# Sheet2.net
KiCad netlist of a schematic drawn in Altium Designer
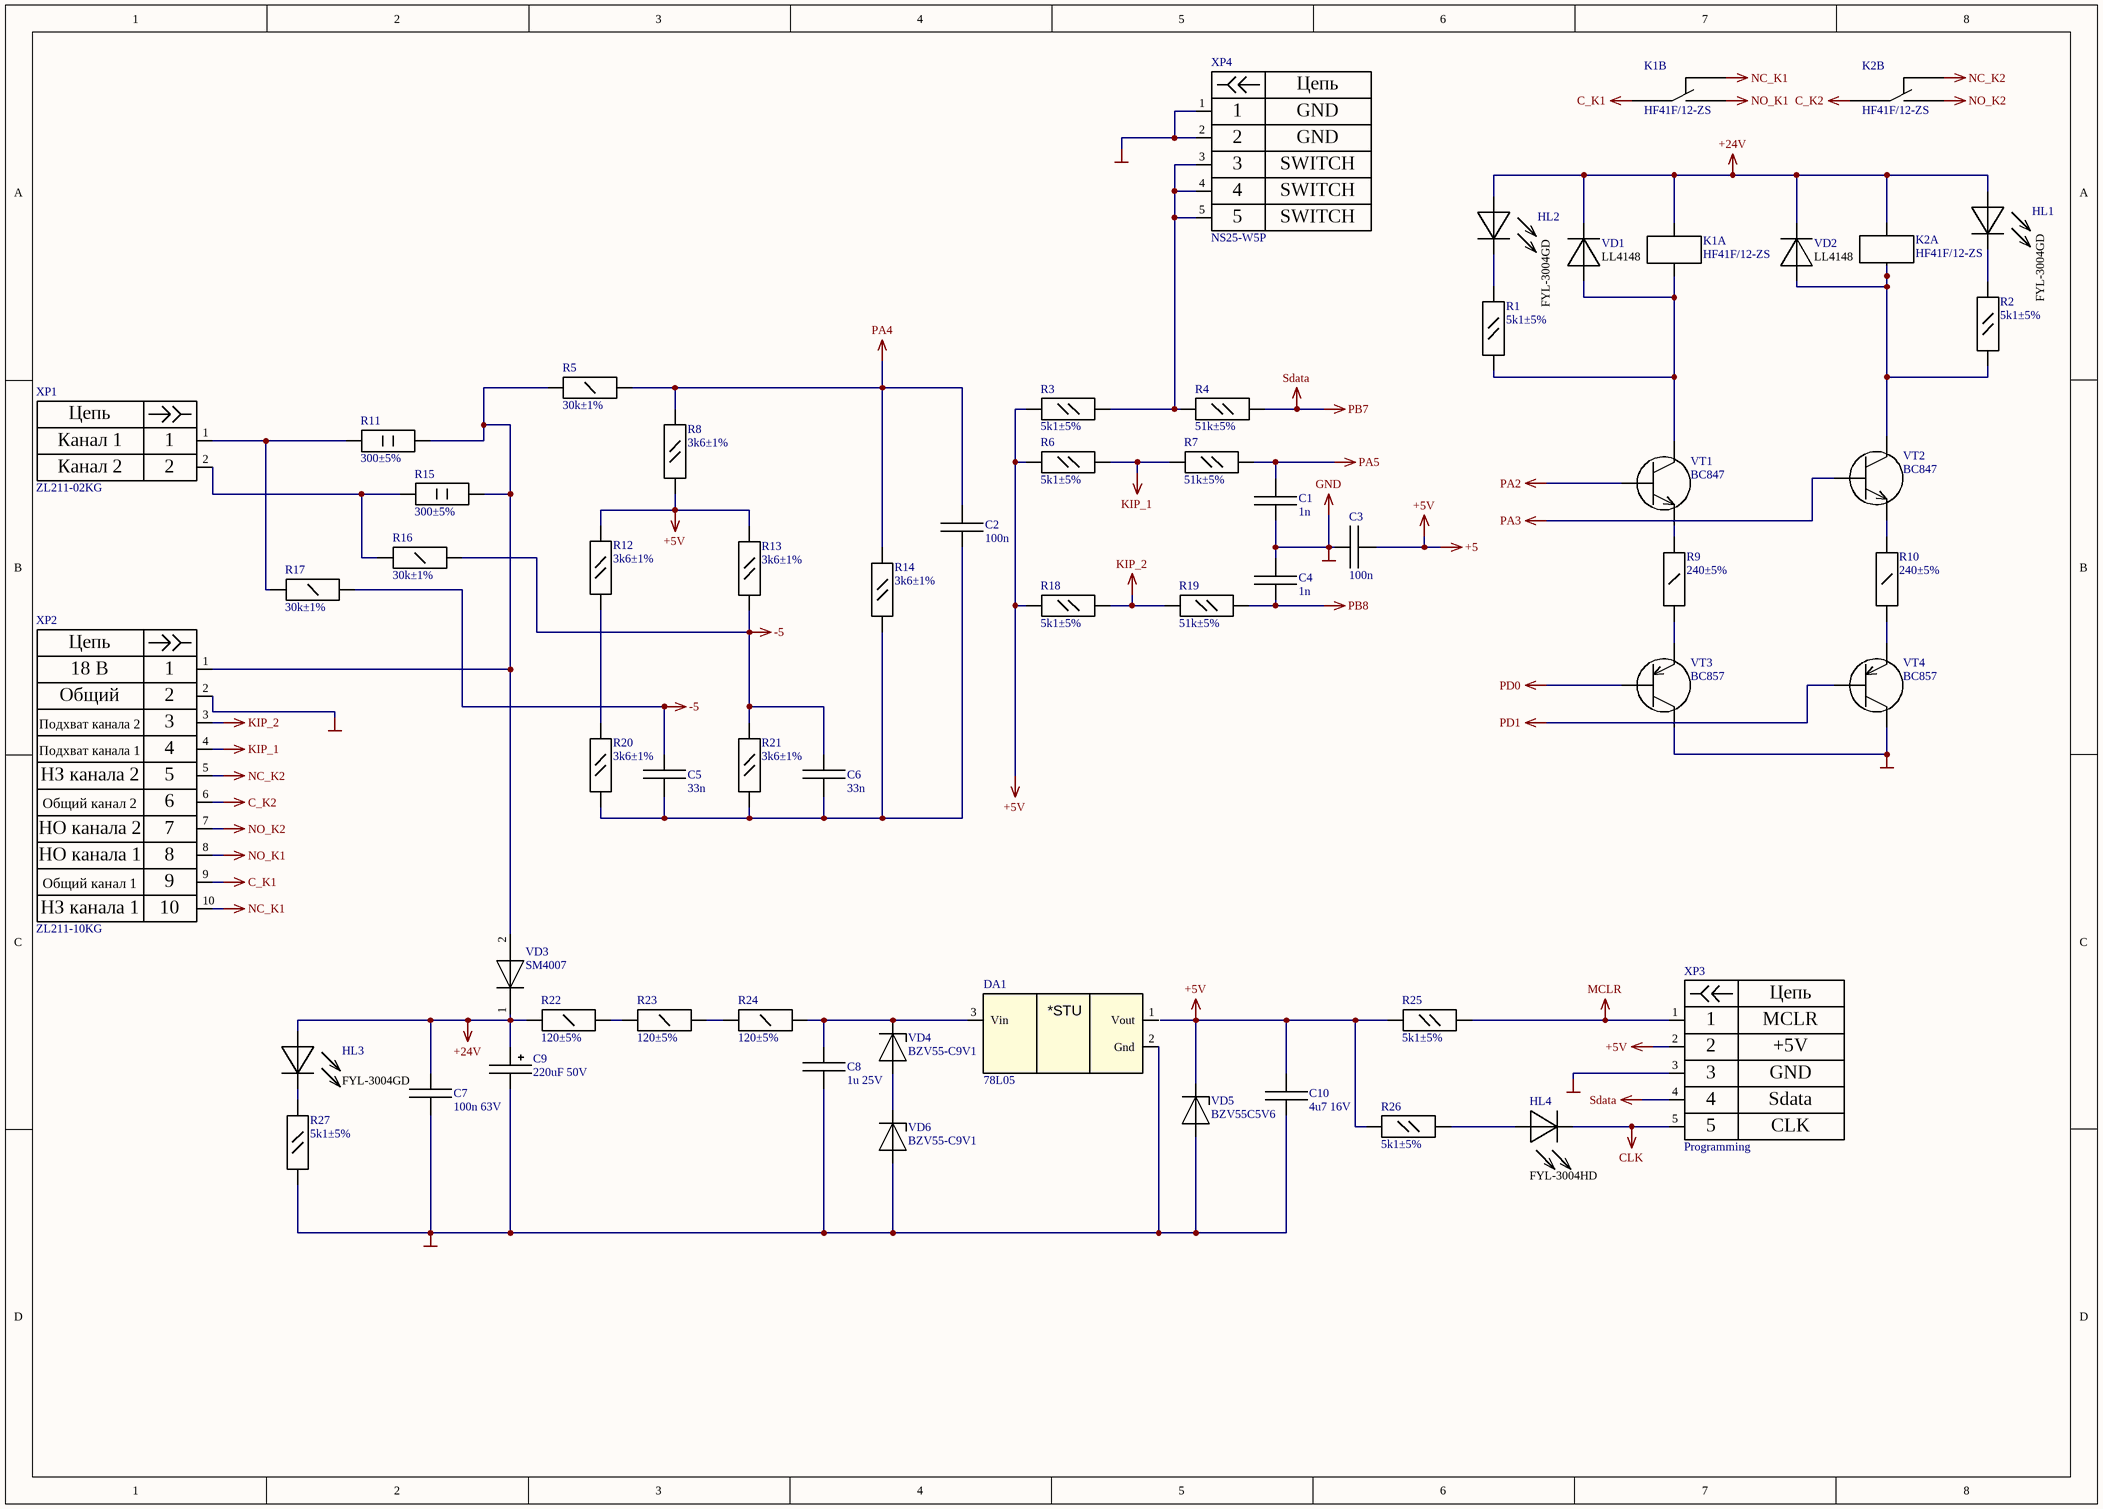
[diagram p0: Sheet2.SchDoc]

(export (version "E")
  (design (tool "Eeschema 10.0.6"))
  (components
    (comp (ref "C1") (value "1n") (footprint "Cap Ceramic 0805") (libsource (lib "Россыпь") (part "CerCap")))
    (comp (ref "C2")
      (value "100n")
      (footprint "Cap Ceramic 0805")
      (libsource (lib "Россыпь") (part "CerCap"))
    )
    (comp (ref "C3")
      (value "100n")
      (footprint "Cap Ceramic 0805")
      (libsource (lib "Россыпь") (part "CerCap"))
    )
    (comp (ref "C4") (value "1n") (footprint "Cap Ceramic 0805") (libsource (lib "Россыпь") (part "CerCap")))
    (comp (ref "C5") (value "33n") (footprint "Cap Ceramic 0805") (libsource (lib "Россыпь") (part "CerCap")))
    (comp (ref "C6") (value "33n") (footprint "Cap Ceramic 0805") (libsource (lib "Россыпь") (part "CerCap")))
    (comp (ref "C7")
      (value "100n 63V")
      (footprint "Cap Ceramic 0805")
      (libsource (lib "Россыпь") (part "CerCap"))
    )
    (comp (ref "C8")
      (value "1u 25V")
      (footprint "Cap Ceramic 0805")
      (libsource (lib "Россыпь") (part "CerCap"))
    )
    (comp (ref "C9")
      (value "220uF 50V")
      (footprint "Cap electro d5x2.05mm")
      (libsource (lib "Россыпь") (part "ECap"))
    )
    (comp (ref "C10")
      (value "4u7 16V")
      (footprint "Cap Ceramic 0805")
      (libsource (lib "Россыпь") (part "CerCap"))
    )
    (comp (ref "DA1") (value "78L05") (footprint "SOT-89") (libsource (lib "Россыпь") (part "78L05")))
    (comp (ref "HL1") (value "FYL-3004GD") (footprint "LED 0805") (libsource (lib "Россыпь") (part "LED")))
    (comp (ref "HL2") (value "FYL-3004GD") (footprint "LED 0805") (libsource (lib "Россыпь") (part "LED")))
    (comp (ref "HL3") (value "FYL-3004GD") (footprint "LED 0805") (libsource (lib "Россыпь") (part "LED")))
    (comp (ref "HL4") (value "FYL-3004HD") (footprint "LED 0805") (libsource (lib "Россыпь") (part "LED")))
    (comp (ref "K1")
      (value "HF41F/12-ZS")
      (footprint "HF41F_12-ZS")
      (libsource (lib "Schlib1") (part "HF41F_12-ZS"))
    )
    (comp (ref "K2")
      (value "HF41F/12-ZS")
      (footprint "HF41F_12-ZS")
      (libsource (lib "Schlib1") (part "HF41F_12-ZS"))
    )
    (comp (ref "R1")
      (value "5k1±5%")
      (footprint "Resistor 0805")
      (libsource (lib "Россыпь") (part "Resistor 0,125W"))
    )
    (comp (ref "R2")
      (value "5k1±5%")
      (footprint "Resistor 0805")
      (libsource (lib "Россыпь") (part "Resistor 0,125W"))
    )
    (comp (ref "R3")
      (value "5k1±5%")
      (footprint "Resistor 0805")
      (libsource (lib "Россыпь") (part "Resistor 0,125W"))
    )
    (comp (ref "R4")
      (value "51k±5%")
      (footprint "Resistor 0805")
      (libsource (lib "Россыпь") (part "Resistor 0,125W"))
    )
    (comp (ref "R5")
      (value "30k±1%")
      (footprint "Resistor 1206")
      (libsource (lib "Schlib1") (part "Resistor 0.5W"))
    )
    (comp (ref "R6")
      (value "5k1±5%")
      (footprint "Resistor 0805")
      (libsource (lib "Россыпь") (part "Resistor 0,125W"))
    )
    (comp (ref "R7")
      (value "51k±5%")
      (footprint "Resistor 0805")
      (libsource (lib "Россыпь") (part "Resistor 0,125W"))
    )
    (comp (ref "R8")
      (value "3k6±1%")
      (footprint "Resistor 0805")
      (libsource (lib "Россыпь") (part "Resistor 0,125W"))
    )
    (comp (ref "R9")
      (value "240±5%")
      (footprint "Resistor 1206")
      (libsource (lib "Schlib1") (part "Resistor 0,25W"))
    )
    (comp (ref "R10")
      (value "240±5%")
      (footprint "Resistor 1206")
      (libsource (lib "Schlib1") (part "Resistor 0,25W"))
    )
    (comp (ref "R11")
      (value "300±5%")
      (footprint "Resistor 2W d5.08x20.32 axial")
      (libsource (lib "Россыпь") (part "Resistor 2W"))
    )
    (comp (ref "R12")
      (value "3k6±1%")
      (footprint "Resistor 0805")
      (libsource (lib "Россыпь") (part "Resistor 0,125W"))
    )
    (comp (ref "R13")
      (value "3k6±1%")
      (footprint "Resistor 0805")
      (libsource (lib "Россыпь") (part "Resistor 0,125W"))
    )
    (comp (ref "R14")
      (value "3k6±1%")
      (footprint "Resistor 0805")
      (libsource (lib "Россыпь") (part "Resistor 0,125W"))
    )
    (comp (ref "R15")
      (value "300±5%")
      (footprint "Resistor 2W d5.08x20.32 axial")
      (libsource (lib "Россыпь") (part "Resistor 2W"))
    )
    (comp (ref "R16")
      (value "30k±1%")
      (footprint "Resistor 1206")
      (libsource (lib "Schlib1") (part "Resistor 0.5W"))
    )
    (comp (ref "R17")
      (value "30k±1%")
      (footprint "Resistor 1206")
      (libsource (lib "Schlib1") (part "Resistor 0.5W"))
    )
    (comp (ref "R18")
      (value "5k1±5%")
      (footprint "Resistor 0805")
      (libsource (lib "Россыпь") (part "Resistor 0,125W"))
    )
    (comp (ref "R19")
      (value "51k±5%")
      (footprint "Resistor 0805")
      (libsource (lib "Россыпь") (part "Resistor 0,125W"))
    )
    (comp (ref "R20")
      (value "3k6±1%")
      (footprint "Resistor 0805")
      (libsource (lib "Россыпь") (part "Resistor 0,125W"))
    )
    (comp (ref "R21")
      (value "3k6±1%")
      (footprint "Resistor 0805")
      (libsource (lib "Россыпь") (part "Resistor 0,125W"))
    )
    (comp (ref "R22")
      (value "120±5%")
      (footprint "Resistor 1206")
      (libsource (lib "Россыпь") (part "Resistor 0,25W"))
    )
    (comp (ref "R23")
      (value "120±5%")
      (footprint "Resistor 1206")
      (libsource (lib "Россыпь") (part "Resistor 0,25W"))
    )
    (comp (ref "R24")
      (value "120±5%")
      (footprint "Resistor 1206")
      (libsource (lib "Россыпь") (part "Resistor 0,25W"))
    )
    (comp (ref "R25")
      (value "5k1±5%")
      (footprint "Resistor 0805")
      (libsource (lib "Schlib1") (part "Resistor 0,125W"))
    )
    (comp (ref "R26")
      (value "5k1±5%")
      (footprint "Resistor 0805")
      (libsource (lib "Schlib1") (part "Resistor 0,125W"))
    )
    (comp (ref "R27")
      (value "5k1±5%")
      (footprint "Resistor 0805")
      (libsource (lib "Schlib1") (part "Resistor 0,125W"))
    )
    (comp (ref "VD1") (value "LL4148") (footprint "SOD80C") (libsource (lib "Россыпь") (part "LL4148")))
    (comp (ref "VD2") (value "LL4148") (footprint "SOD80C") (libsource (lib "Россыпь") (part "LL4148")))
    (comp (ref "VD3") (value "SM4007") (footprint "SM4007") (libsource (lib "Schlib1") (part "SM4007")))
    (comp (ref "VD4")
      (value "BZV55-C9V1")
      (footprint "BZV55C9V1")
      (libsource (lib "Schlib1") (part "BZV55C9V1"))
    )
    (comp (ref "VD5")
      (value "BZV55C5V6")
      (footprint "BZV55C5V6")
      (libsource (lib "Schlib1") (part "BZV55C5V6"))
    )
    (comp (ref "VD6")
      (value "BZV55-C9V1")
      (footprint "BZV55C9V1")
      (libsource (lib "Schlib1") (part "BZV55C9V1"))
    )
    (comp (ref "VT1") (value "BC847") (footprint "SOT-23-3") (libsource (lib "Россыпь") (part "BC847")))
    (comp (ref "VT2") (value "BC847") (footprint "SOT-23-3") (libsource (lib "Россыпь") (part "BC847")))
    (comp (ref "VT3") (value "BC857") (footprint "SOT-23-3") (libsource (lib "Россыпь") (part "BC857")))
    (comp (ref "VT4") (value "BC857") (footprint "SOT-23-3") (libsource (lib "Россыпь") (part "BC857")))
    (comp (ref "XP1")
      (value "ZL211-02KG")
      (footprint "Pins 1x2")
      (fields (field (name "NAME1") "Канал 1") (field (name "NAME") "Цепь") (field (name "NAME2") "Канал 2"))
      (libsource (lib "Россыпь") (part "Pins 1x2"))
    )
    (comp (ref "XP2")
      (value "ZL211-10KG")
      (footprint "Pins 1x10")
      (fields
        (field (name "NAME1") "18 В")
        (field (name "NAME2") "Общий")
        (field (name "NAME3") "Подхват канала 2")
        (field (name "NAME") "Цепь")
        (field (name "NAME4") "Подхват канала 1")
        (field (name "NAME5") "НЗ канала 2")
        (field (name "NAME6") "Общий канал 2")
        (field (name "NAME7") "НО канала 2")
        (field (name "NAME8") "НО канала 1")
        (field (name "NAME9") "Общий канал 1")
        (field (name "NAME10") "НЗ канала 1")
      )
      (libsource (lib "Россыпь") (part "Pins 1x10"))
    )
    (comp (ref "XP3")
      (value "Programming")
      (footprint "WF-05")
      (fields
        (field (name "NAME1") "MCLR")
        (field (name "NAME") "Цепь")
        (field (name "NAME2") "+5V")
        (field (name "NAME3") "GND")
        (field (name "NAME4") "Sdata")
        (field (name "NAME5") "CLK")
      )
      (libsource (lib "Россыпь") (part "Pins 1x5"))
    )
    (comp (ref "XP4")
      (value "NS25-W5P")
      (footprint "WF-05")
      (fields
        (field (name "NAME1") "GND")
        (field (name "NAME") "Цепь")
        (field (name "NAME2") "GND")
        (field (name "NAME3") "SWITCH")
        (field (name "NAME4") "SWITCH")
        (field (name "NAME5") "SWITCH")
      )
      (libsource (lib "Россыпь") (part "Pins 1x5"))
    )
  )
  (nets
    (net (code "1") (name "+5") (class "Default")
      (node (ref "C10") (pin "2") (pinfunction "2_2") (pintype "passive"))
      (node (ref "C3") (pin "2") (pinfunction "2_2") (pintype "passive"))
      (node (ref "R12") (pin "2") (pinfunction "2_2") (pintype "passive"))
      (node (ref "R13") (pin "2") (pinfunction "2_2") (pintype "passive"))
      (node (ref "R18") (pin "1") (pinfunction "1_1") (pintype "passive"))
      (node (ref "R25") (pin "1") (pinfunction "1_1") (pintype "passive"))
      (node (ref "R26") (pin "1") (pinfunction "1_1") (pintype "passive"))
      (node (ref "R3") (pin "1") (pinfunction "1_1") (pintype "passive"))
      (node (ref "R6") (pin "1") (pinfunction "1_1") (pintype "passive"))
      (node (ref "R8") (pin "1") (pinfunction "1_1") (pintype "passive"))
      (node (ref "VD5") (pin "9") (pinfunction "9_9") (pintype "passive"))
      (node (ref "XP3") (pin "2") (pinfunction "2_2") (pintype "passive"))
    )
    (net (code "2") (name "+24V") (class "Default")
      (node (ref "C7") (pin "1") (pinfunction "1_1") (pintype "passive"))
      (node (ref "C9") (pin "2") (pinfunction "2_2") (pintype "passive"))
      (node (ref "HL1") (pin "1") (pinfunction "A_1") (pintype "passive"))
      (node (ref "HL2") (pin "1") (pinfunction "A_1") (pintype "passive"))
      (node (ref "HL3") (pin "1") (pinfunction "A_1") (pintype "passive"))
      (node (ref "K1") (pin "10") (pinfunction "10_10") (pintype "passive"))
      (node (ref "K2") (pin "10") (pinfunction "10_10") (pintype "passive"))
      (node (ref "R22") (pin "1") (pinfunction "1_1") (pintype "passive"))
      (node (ref "VD1") (pin "2") (pinfunction "K_2") (pintype "passive"))
      (node (ref "VD2") (pin "2") (pinfunction "K_2") (pintype "passive"))
      (node (ref "VD3") (pin "1") (pinfunction "2_1") (pintype "passive"))
    )
    (net (code "3") (name "-5") (class "Default")
      (node (ref "C1") (pin "1") (pinfunction "1_1") (pintype "passive"))
      (node (ref "C10") (pin "1") (pinfunction "1_1") (pintype "passive"))
      (node (ref "C3") (pin "1") (pinfunction "1_1") (pintype "passive"))
      (node (ref "C4") (pin "2") (pinfunction "2_2") (pintype "passive"))
      (node (ref "C5") (pin "1") (pinfunction "1_1") (pintype "passive"))
      (node (ref "C6") (pin "1") (pinfunction "1_1") (pintype "passive"))
      (node (ref "C7") (pin "2") (pinfunction "2_2") (pintype "passive"))
      (node (ref "C8") (pin "2") (pinfunction "2_2") (pintype "passive"))
      (node (ref "C9") (pin "1") (pinfunction "1_1") (pintype "passive"))
      (node (ref "DA1") (pin "2") (pinfunction "Gnd_2") (pintype "passive"))
      (node (ref "R13") (pin "1") (pinfunction "1_1") (pintype "passive"))
      (node (ref "R16") (pin "2") (pinfunction "2_2") (pintype "passive"))
      (node (ref "R17") (pin "2") (pinfunction "2_2") (pintype "passive"))
      (node (ref "R21") (pin "2") (pinfunction "2_2") (pintype "passive"))
      (node (ref "R27") (pin "1") (pinfunction "1_1") (pintype "passive"))
      (node (ref "VD5") (pin "8") (pinfunction "8_8") (pintype "passive"))
      (node (ref "VD6") (pin "8") (pinfunction "8_8") (pintype "passive"))
      (node (ref "VT3") (pin "3") (pinfunction "K_3") (pintype "passive"))
      (node (ref "VT4") (pin "3") (pinfunction "K_3") (pintype "passive"))
      (node (ref "XP2") (pin "2") (pinfunction "2_2") (pintype "passive"))
      (node (ref "XP3") (pin "3") (pinfunction "3_3") (pintype "passive"))
      (node (ref "XP4") (pin "1") (pinfunction "1_1") (pintype "passive"))
      (node (ref "XP4") (pin "2") (pinfunction "2_2") (pintype "passive"))
    )
    (net (code "4") (name "CLK") (class "Default")
      (node (ref "HL4") (pin "2") (pinfunction "K_2") (pintype "passive"))
      (node (ref "XP3") (pin "5") (pinfunction "5_5") (pintype "passive"))
    )
    (net (code "5") (name "C_K1") (class "Default")
      (node (ref "K1") (pin "14") (pinfunction "14_14") (pintype "passive"))
      (node (ref "XP2") (pin "9") (pinfunction "9_9") (pintype "passive"))
    )
    (net (code "6") (name "C_K2") (class "Default")
      (node (ref "K2") (pin "14") (pinfunction "14_14") (pintype "passive"))
      (node (ref "XP2") (pin "6") (pinfunction "6_6") (pintype "passive"))
    )
    (net (code "7") (name "KIP_1") (class "Default")
      (node (ref "R6") (pin "2") (pinfunction "2_2") (pintype "passive"))
      (node (ref "R7") (pin "1") (pinfunction "1_1") (pintype "passive"))
      (node (ref "XP2") (pin "4") (pinfunction "4_4") (pintype "passive"))
    )
    (net (code "8") (name "KIP_2") (class "Default")
      (node (ref "R18") (pin "2") (pinfunction "2_2") (pintype "passive"))
      (node (ref "R19") (pin "1") (pinfunction "1_1") (pintype "passive"))
      (node (ref "XP2") (pin "3") (pinfunction "3_3") (pintype "passive"))
    )
    (net (code "9") (name "MCLR") (class "Default")
      (node (ref "R25") (pin "2") (pinfunction "2_2") (pintype "passive"))
      (node (ref "XP3") (pin "1") (pinfunction "1_1") (pintype "passive"))
    )
    (net (code "10") (name "NC_K1") (class "Default")
      (node (ref "K1") (pin "12") (pinfunction "12_12") (pintype "passive"))
      (node (ref "XP2") (pin "10") (pinfunction "10_10") (pintype "passive"))
    )
    (net (code "11") (name "NC_K2") (class "Default")
      (node (ref "K2") (pin "12") (pinfunction "12_12") (pintype "passive"))
      (node (ref "XP2") (pin "5") (pinfunction "5_5") (pintype "passive"))
    )
    (net (code "12") (name "NO_K1") (class "Default")
      (node (ref "K1") (pin "13") (pinfunction "13_13") (pintype "passive"))
      (node (ref "XP2") (pin "8") (pinfunction "8_8") (pintype "passive"))
    )
    (net (code "13") (name "NO_K2") (class "Default")
      (node (ref "K2") (pin "13") (pinfunction "13_13") (pintype "passive"))
      (node (ref "XP2") (pin "7") (pinfunction "7_7") (pintype "passive"))
    )
    (net (code "14") (name "Net-(C2-Pad1)") (class "Default")
      (node (ref "C2") (pin "1") (pinfunction "1_1") (pintype "passive"))
      (node (ref "C5") (pin "2") (pinfunction "2_2") (pintype "passive"))
      (node (ref "C6") (pin "2") (pinfunction "2_2") (pintype "passive"))
      (node (ref "R14") (pin "1") (pinfunction "1_1") (pintype "passive"))
      (node (ref "R20") (pin "1") (pinfunction "1_1") (pintype "passive"))
      (node (ref "R21") (pin "1") (pinfunction "1_1") (pintype "passive"))
    )
    (net (code "15") (name "Net-(DA1-Vin)") (class "Default")
      (node (ref "C8") (pin "1") (pinfunction "1_1") (pintype "passive"))
      (node (ref "DA1") (pin "3") (pinfunction "Vin_3") (pintype "passive"))
      (node (ref "R24") (pin "2") (pinfunction "2_2") (pintype "passive"))
      (node (ref "VD4") (pin "9") (pinfunction "9_9") (pintype "passive"))
    )
    (net (code "16") (name "Net-(HL1-K)") (class "Default")
      (node (ref "HL1") (pin "2") (pinfunction "K_2") (pintype "passive"))
      (node (ref "R2") (pin "2") (pinfunction "2_2") (pintype "passive"))
    )
    (net (code "17") (name "Net-(HL2-K)") (class "Default")
      (node (ref "HL2") (pin "2") (pinfunction "K_2") (pintype "passive"))
      (node (ref "R1") (pin "2") (pinfunction "2_2") (pintype "passive"))
    )
    (net (code "18") (name "Net-(HL3-K)") (class "Default")
      (node (ref "HL3") (pin "2") (pinfunction "K_2") (pintype "passive"))
      (node (ref "R27") (pin "2") (pinfunction "2_2") (pintype "passive"))
    )
    (net (code "19") (name "Net-(HL4-A)") (class "Default")
      (node (ref "HL4") (pin "1") (pinfunction "A_1") (pintype "passive"))
      (node (ref "R26") (pin "2") (pinfunction "2_2") (pintype "passive"))
    )
    (net (code "20") (name "Net-(R3-Pad2)") (class "Default")
      (node (ref "R3") (pin "2") (pinfunction "2_2") (pintype "passive"))
      (node (ref "R4") (pin "1") (pinfunction "1_1") (pintype "passive"))
      (node (ref "XP4") (pin "3") (pinfunction "3_3") (pintype "passive"))
      (node (ref "XP4") (pin "4") (pinfunction "4_4") (pintype "passive"))
      (node (ref "XP4") (pin "5") (pinfunction "5_5") (pintype "passive"))
    )
    (net (code "21") (name "Net-(R11-Pad1)") (class "Default")
      (node (ref "R11") (pin "1") (pinfunction "1_1") (pintype "passive"))
      (node (ref "R17") (pin "1") (pinfunction "1_1") (pintype "passive"))
      (node (ref "XP1") (pin "1") (pinfunction "1_1") (pintype "passive"))
    )
    (net (code "22") (name "Net-(R12-Pad1)") (class "Default")
      (node (ref "R12") (pin "1") (pinfunction "1_1") (pintype "passive"))
      (node (ref "R20") (pin "2") (pinfunction "2_2") (pintype "passive"))
    )
    (net (code "23") (name "Net-(R15-Pad1)") (class "Default")
      (node (ref "R15") (pin "1") (pinfunction "1_1") (pintype "passive"))
      (node (ref "R16") (pin "1") (pinfunction "1_1") (pintype "passive"))
      (node (ref "XP1") (pin "2") (pinfunction "2_2") (pintype "passive"))
    )
    (net (code "24") (name "Net-(R22-Pad2)") (class "Default")
      (node (ref "R22") (pin "2") (pinfunction "2_2") (pintype "passive"))
      (node (ref "R23") (pin "1") (pinfunction "1_1") (pintype "passive"))
    )
    (net (code "25") (name "Net-(R23-Pad2)") (class "Default")
      (node (ref "R23") (pin "2") (pinfunction "2_2") (pintype "passive"))
      (node (ref "R24") (pin "1") (pinfunction "1_1") (pintype "passive"))
    )
    (net (code "26") (name "Net-(VD1-A)") (class "Default")
      (node (ref "K1") (pin "11") (pinfunction "11_11") (pintype "passive"))
      (node (ref "R1") (pin "1") (pinfunction "1_1") (pintype "passive"))
      (node (ref "VD1") (pin "1") (pinfunction "A_1") (pintype "passive"))
      (node (ref "VT1") (pin "3") (pinfunction "K_3") (pintype "passive"))
    )
    (net (code "27") (name "Net-(VD2-A)") (class "Default")
      (node (ref "K2") (pin "11") (pinfunction "11_11") (pintype "passive"))
      (node (ref "R2") (pin "1") (pinfunction "1_1") (pintype "passive"))
      (node (ref "VD2") (pin "1") (pinfunction "A_1") (pintype "passive"))
      (node (ref "VT2") (pin "3") (pinfunction "K_3") (pintype "passive"))
    )
    (net (code "28") (name "Net-(VD3-4)") (class "Default")
      (node (ref "R11") (pin "2") (pinfunction "2_2") (pintype "passive"))
      (node (ref "R15") (pin "2") (pinfunction "2_2") (pintype "passive"))
      (node (ref "R5") (pin "1") (pinfunction "1_1") (pintype "passive"))
      (node (ref "VD3") (pin "2") (pinfunction "4_2") (pintype "passive"))
      (node (ref "XP2") (pin "1") (pinfunction "1_1") (pintype "passive"))
    )
    (net (code "29") (name "Net-(VD4-Pad8)") (class "Default")
      (node (ref "VD4") (pin "8") (pinfunction "8_8") (pintype "passive"))
      (node (ref "VD6") (pin "9") (pinfunction "9_9") (pintype "passive"))
    )
    (net (code "30") (name "Net-(VT1-E)") (class "Default")
      (node (ref "R9") (pin "2") (pinfunction "2_2") (pintype "passive"))
      (node (ref "VT1") (pin "2") (pinfunction "E_2") (pintype "passive"))
    )
    (net (code "31") (name "Net-(VT2-E)") (class "Default")
      (node (ref "R10") (pin "2") (pinfunction "2_2") (pintype "passive"))
      (node (ref "VT2") (pin "2") (pinfunction "E_2") (pintype "passive"))
    )
    (net (code "32") (name "Net-(VT3-E)") (class "Default")
      (node (ref "R9") (pin "1") (pinfunction "1_1") (pintype "passive"))
      (node (ref "VT3") (pin "2") (pinfunction "E_2") (pintype "passive"))
    )
    (net (code "33") (name "Net-(VT4-E)") (class "Default")
      (node (ref "R10") (pin "1") (pinfunction "1_1") (pintype "passive"))
      (node (ref "VT4") (pin "2") (pinfunction "E_2") (pintype "passive"))
    )
    (net (code "34") (name "PA2") (class "Default")
      (node (ref "VT1") (pin "1") (pinfunction "B_1") (pintype "passive"))
    )
    (net (code "35") (name "PA3") (class "Default")
      (node (ref "VT2") (pin "1") (pinfunction "B_1") (pintype "passive"))
    )
    (net (code "36") (name "PA4") (class "Default")
      (node (ref "C2") (pin "2") (pinfunction "2_2") (pintype "passive"))
      (node (ref "R14") (pin "2") (pinfunction "2_2") (pintype "passive"))
      (node (ref "R5") (pin "2") (pinfunction "2_2") (pintype "passive"))
      (node (ref "R8") (pin "2") (pinfunction "2_2") (pintype "passive"))
    )
    (net (code "37") (name "PA5") (class "Default")
      (node (ref "C1") (pin "2") (pinfunction "2_2") (pintype "passive"))
      (node (ref "R7") (pin "2") (pinfunction "2_2") (pintype "passive"))
    )
    (net (code "38") (name "PB7") (class "Default")
      (node (ref "R4") (pin "2") (pinfunction "2_2") (pintype "passive"))
      (node (ref "XP3") (pin "4") (pinfunction "4_4") (pintype "passive"))
    )
    (net (code "39") (name "PB8") (class "Default")
      (node (ref "C4") (pin "1") (pinfunction "1_1") (pintype "passive"))
      (node (ref "R19") (pin "2") (pinfunction "2_2") (pintype "passive"))
    )
    (net (code "40") (name "PD0") (class "Default")
      (node (ref "VT3") (pin "1") (pinfunction "B_1") (pintype "passive"))
    )
    (net (code "41") (name "PD1") (class "Default")
      (node (ref "VT4") (pin "1") (pinfunction "B_1") (pintype "passive"))
    )
    (net (code "42") (name "unconnected-(DA1-Vout-Pad1)") (class "Default")
      (node (ref "DA1") (pin "1") (pinfunction "Vout_1") (pintype "passive"))
    )
  )
)
